# Planta_2_subamortiguada.net
KiCad netlist of a schematic drawn in EAGLE
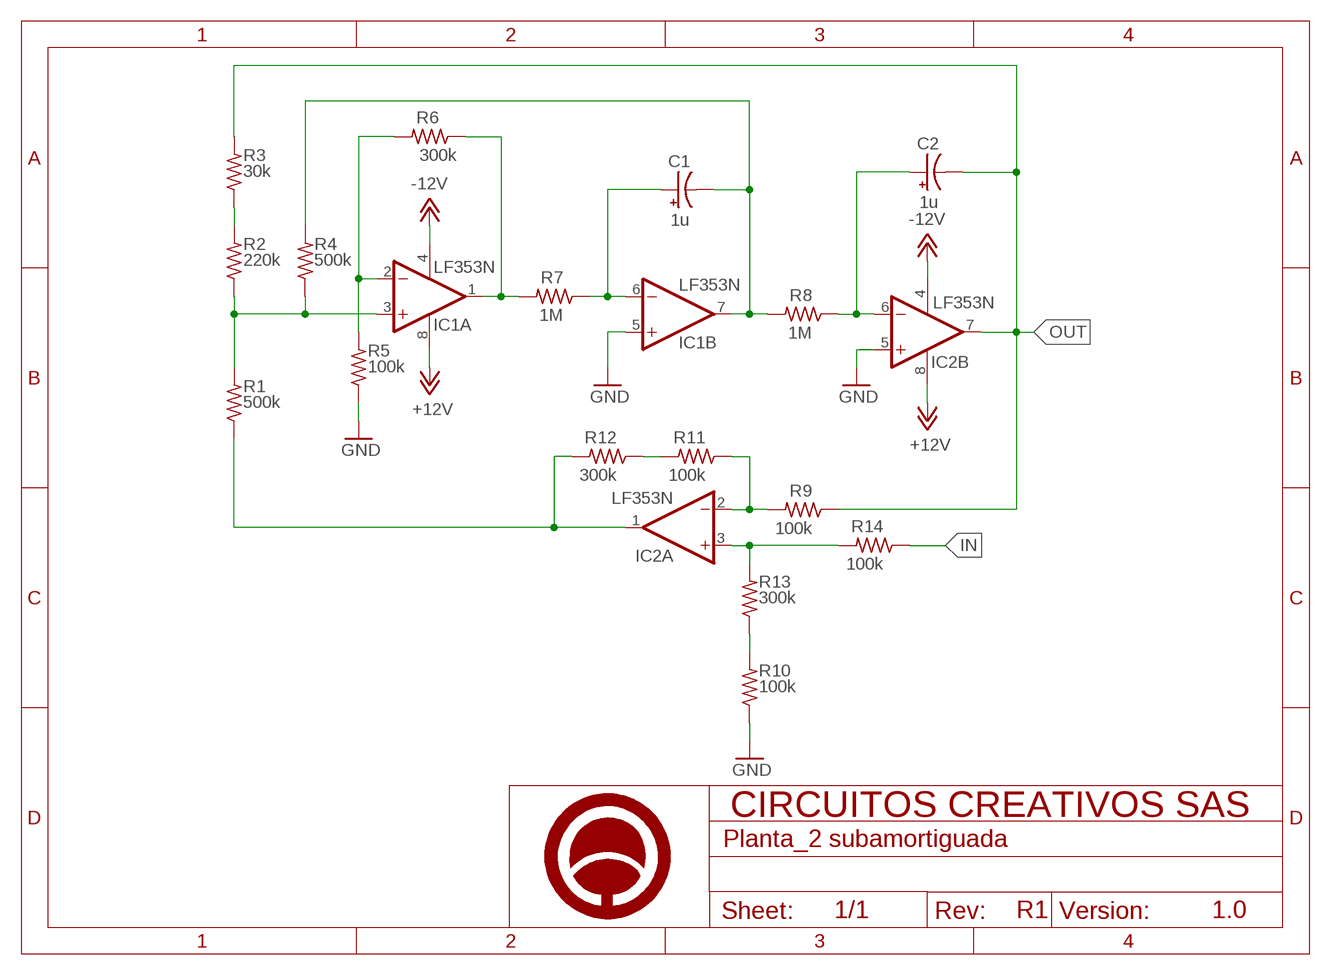
[diagram p0: schematic, sheet 1]

(export (version "E")
  (design (tool "Eeschema 10.0.6"))
  (components
    (comp (ref "C1")
      (value "1u")
      (footprint "eagle-import:E2-5")
      (libsource (lib "eagle-import") (part "CPOL-USE2-5"))
    )
    (comp (ref "C2")
      (value "1u")
      (footprint "eagle-import:E2-5")
      (libsource (lib "eagle-import") (part "CPOL-USE2-5"))
    )
    (comp (ref "F1")
      (value "A5_HORIZONTAL")
      (footprint "eagle-import:LOGO")
      (libsource (lib "eagle-import") (part "A5_HORIZONTAL"))
    )
    (comp (ref "IC1")
      (value "LF353N")
      (footprint "eagle-import:DIL08")
      (libsource (lib "eagle-import") (part "LF353N"))
    )
    (comp (ref "IC2")
      (value "LF353N")
      (footprint "eagle-import:DIL08")
      (libsource (lib "eagle-import") (part "LF353N"))
    )
    (comp (ref "R1")
      (value "500k")
      (footprint "eagle-import:0204_7")
      (libsource (lib "eagle-import") (part "R-US_0204/7"))
    )
    (comp (ref "R2")
      (value "220k")
      (footprint "eagle-import:0204_7")
      (libsource (lib "eagle-import") (part "R-US_0204/7"))
    )
    (comp (ref "R3")
      (value "30k")
      (footprint "eagle-import:0204_7")
      (libsource (lib "eagle-import") (part "R-US_0204/7"))
    )
    (comp (ref "R4")
      (value "500k")
      (footprint "eagle-import:0204_7")
      (libsource (lib "eagle-import") (part "R-US_0204/7"))
    )
    (comp (ref "R5")
      (value "100k")
      (footprint "eagle-import:0204_7")
      (libsource (lib "eagle-import") (part "R-US_0204/7"))
    )
    (comp (ref "R6")
      (value "300k")
      (footprint "eagle-import:0204_7")
      (libsource (lib "eagle-import") (part "R-US_0204/7"))
    )
    (comp (ref "R7")
      (value "1M")
      (footprint "eagle-import:0204_7")
      (libsource (lib "eagle-import") (part "R-US_0204/7"))
    )
    (comp (ref "R8")
      (value "1M")
      (footprint "eagle-import:0204_7")
      (libsource (lib "eagle-import") (part "R-US_0204/7"))
    )
    (comp (ref "R9")
      (value "100k")
      (footprint "eagle-import:0204_7")
      (libsource (lib "eagle-import") (part "R-US_0204/7"))
    )
    (comp (ref "R10")
      (value "100k")
      (footprint "eagle-import:0204_7")
      (libsource (lib "eagle-import") (part "R-US_0204/7"))
    )
    (comp (ref "R11")
      (value "100k")
      (footprint "eagle-import:0204_7")
      (libsource (lib "eagle-import") (part "R-US_0204/7"))
    )
    (comp (ref "R12")
      (value "300k")
      (footprint "eagle-import:0204_7")
      (libsource (lib "eagle-import") (part "R-US_0204/7"))
    )
    (comp (ref "R13")
      (value "300k")
      (footprint "eagle-import:0204_7")
      (libsource (lib "eagle-import") (part "R-US_0204/7"))
    )
    (comp (ref "R14")
      (value "100k")
      (footprint "eagle-import:0204_7")
      (libsource (lib "eagle-import") (part "R-US_0204/7"))
    )
  )
  (nets
    (net (code "1") (name "+12V") (class "Default")
      (node (ref "IC1") (pin "8") (pinfunction "V+_8") (pintype "power_in"))
      (node (ref "IC2") (pin "8") (pinfunction "V+_8") (pintype "power_in"))
    )
    (net (code "2") (name "-12V") (class "Default")
      (node (ref "IC1") (pin "4") (pinfunction "V-_4") (pintype "power_in"))
      (node (ref "IC2") (pin "4") (pinfunction "V-_4") (pintype "power_in"))
    )
    (net (code "3") (name "GND") (class "Default")
      (node (ref "IC1") (pin "5") (pinfunction "+IN_5") (pintype "input"))
      (node (ref "IC2") (pin "5") (pinfunction "+IN_5") (pintype "input"))
      (node (ref "R10") (pin "1") (pinfunction "1_1") (pintype "passive"))
      (node (ref "R5") (pin "1") (pinfunction "1_1") (pintype "passive"))
    )
    (net (code "4") (name "IN") (class "Default")
      (node (ref "R14") (pin "1") (pinfunction "1_1") (pintype "passive"))
    )
    (net (code "5") (name "Net-(IC1A-+IN)") (class "Default")
      (node (ref "IC1") (pin "3") (pinfunction "+IN_3") (pintype "input"))
      (node (ref "R1") (pin "2") (pinfunction "2_2") (pintype "passive"))
      (node (ref "R2") (pin "1") (pinfunction "1_1") (pintype "passive"))
      (node (ref "R4") (pin "1") (pinfunction "1_1") (pintype "passive"))
    )
    (net (code "6") (name "Net-(IC1A--IN)") (class "Default")
      (node (ref "IC1") (pin "2") (pinfunction "-IN_2") (pintype "input"))
      (node (ref "R5") (pin "2") (pinfunction "2_2") (pintype "passive"))
      (node (ref "R6") (pin "2") (pinfunction "2_2") (pintype "passive"))
    )
    (net (code "7") (name "Net-(IC1A-OUT)") (class "Default")
      (node (ref "IC1") (pin "1") (pinfunction "OUT_1") (pintype "output"))
      (node (ref "R6") (pin "1") (pinfunction "1_1") (pintype "passive"))
      (node (ref "R7") (pin "2") (pinfunction "2_2") (pintype "passive"))
    )
    (net (code "8") (name "Net-(IC1B--IN)") (class "Default")
      (node (ref "C1") (pin "+") (pinfunction "+_+") (pintype "passive"))
      (node (ref "IC1") (pin "6") (pinfunction "-IN_6") (pintype "input"))
      (node (ref "R7") (pin "1") (pinfunction "1_1") (pintype "passive"))
    )
    (net (code "9") (name "Net-(IC1B-OUT)") (class "Default")
      (node (ref "C1") (pin "-") (pinfunction "-_-") (pintype "passive"))
      (node (ref "IC1") (pin "7") (pinfunction "OUT_7") (pintype "output"))
      (node (ref "R4") (pin "2") (pinfunction "2_2") (pintype "passive"))
      (node (ref "R8") (pin "2") (pinfunction "2_2") (pintype "passive"))
    )
    (net (code "10") (name "Net-(IC2A-+IN)") (class "Default")
      (node (ref "IC2") (pin "3") (pinfunction "+IN_3") (pintype "input"))
      (node (ref "R13") (pin "2") (pinfunction "2_2") (pintype "passive"))
      (node (ref "R14") (pin "2") (pinfunction "2_2") (pintype "passive"))
    )
    (net (code "11") (name "Net-(IC2A--IN)") (class "Default")
      (node (ref "IC2") (pin "2") (pinfunction "-IN_2") (pintype "input"))
      (node (ref "R11") (pin "1") (pinfunction "1_1") (pintype "passive"))
      (node (ref "R9") (pin "2") (pinfunction "2_2") (pintype "passive"))
    )
    (net (code "12") (name "Net-(IC2A-OUT)") (class "Default")
      (node (ref "IC2") (pin "1") (pinfunction "OUT_1") (pintype "output"))
      (node (ref "R1") (pin "1") (pinfunction "1_1") (pintype "passive"))
      (node (ref "R12") (pin "2") (pinfunction "2_2") (pintype "passive"))
    )
    (net (code "13") (name "Net-(IC2B--IN)") (class "Default")
      (node (ref "C2") (pin "+") (pinfunction "+_+") (pintype "passive"))
      (node (ref "IC2") (pin "6") (pinfunction "-IN_6") (pintype "input"))
      (node (ref "R8") (pin "1") (pinfunction "1_1") (pintype "passive"))
    )
    (net (code "14") (name "Net-(R2-Pad2)") (class "Default")
      (node (ref "R2") (pin "2") (pinfunction "2_2") (pintype "passive"))
      (node (ref "R3") (pin "1") (pinfunction "1_1") (pintype "passive"))
    )
    (net (code "15") (name "Net-(R10-Pad2)") (class "Default")
      (node (ref "R10") (pin "2") (pinfunction "2_2") (pintype "passive"))
      (node (ref "R13") (pin "1") (pinfunction "1_1") (pintype "passive"))
    )
    (net (code "16") (name "Net-(R11-Pad2)") (class "Default")
      (node (ref "R11") (pin "2") (pinfunction "2_2") (pintype "passive"))
      (node (ref "R12") (pin "1") (pinfunction "1_1") (pintype "passive"))
    )
    (net (code "17") (name "OUT") (class "Default")
      (node (ref "C2") (pin "-") (pinfunction "-_-") (pintype "passive"))
      (node (ref "IC2") (pin "7") (pinfunction "OUT_7") (pintype "output"))
      (node (ref "R3") (pin "2") (pinfunction "2_2") (pintype "passive"))
      (node (ref "R9") (pin "1") (pinfunction "1_1") (pintype "passive"))
    )
  )
)
